# BackPlane.net
KiCad netlist of a schematic drawn in EAGLE
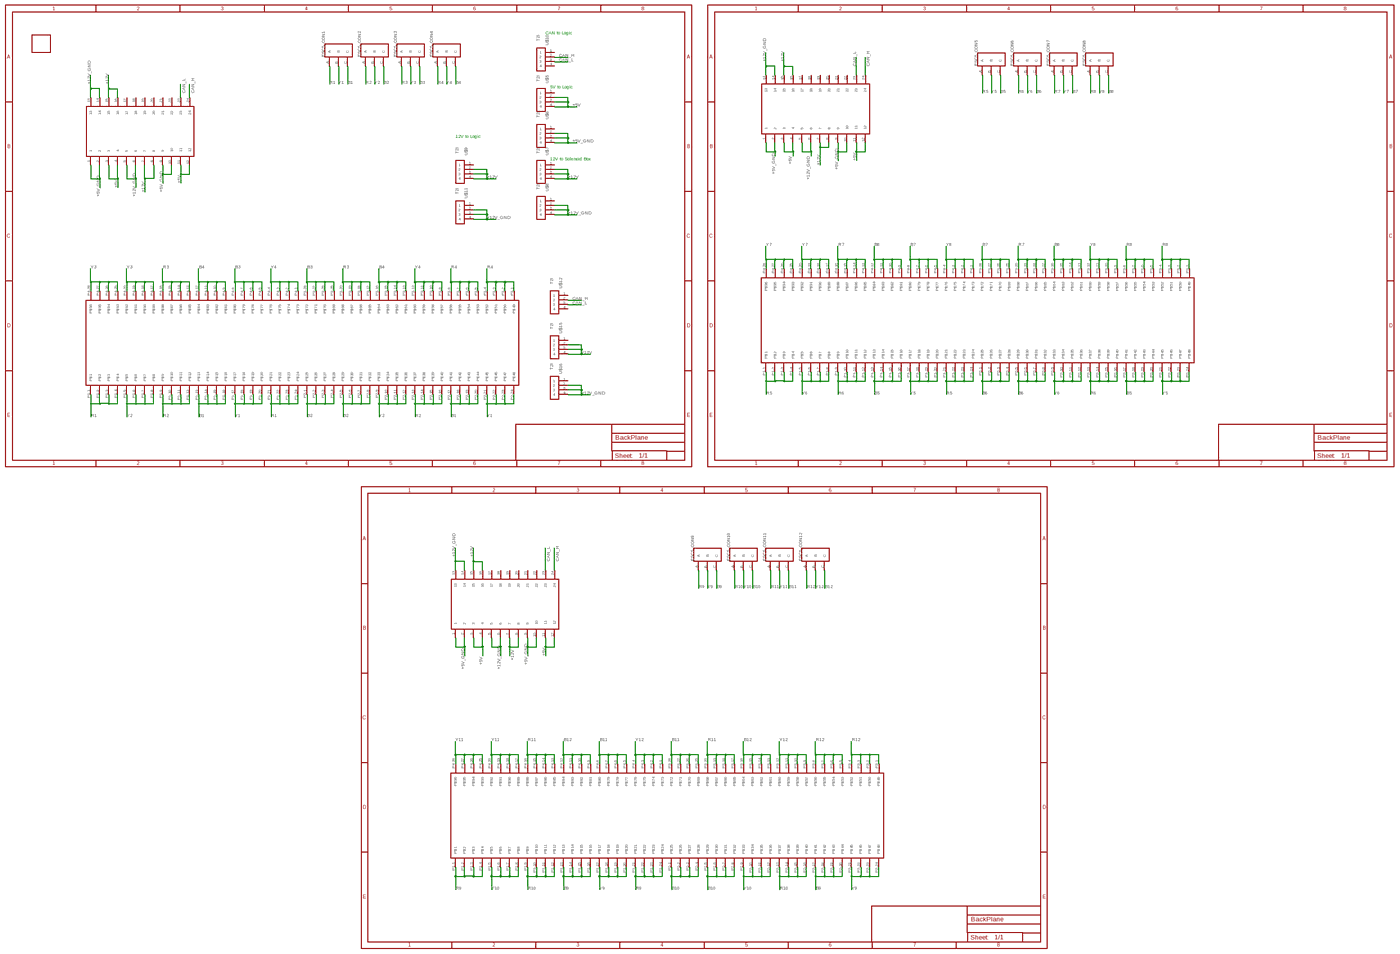
[diagram p0: schematic, sheet 1, overview]
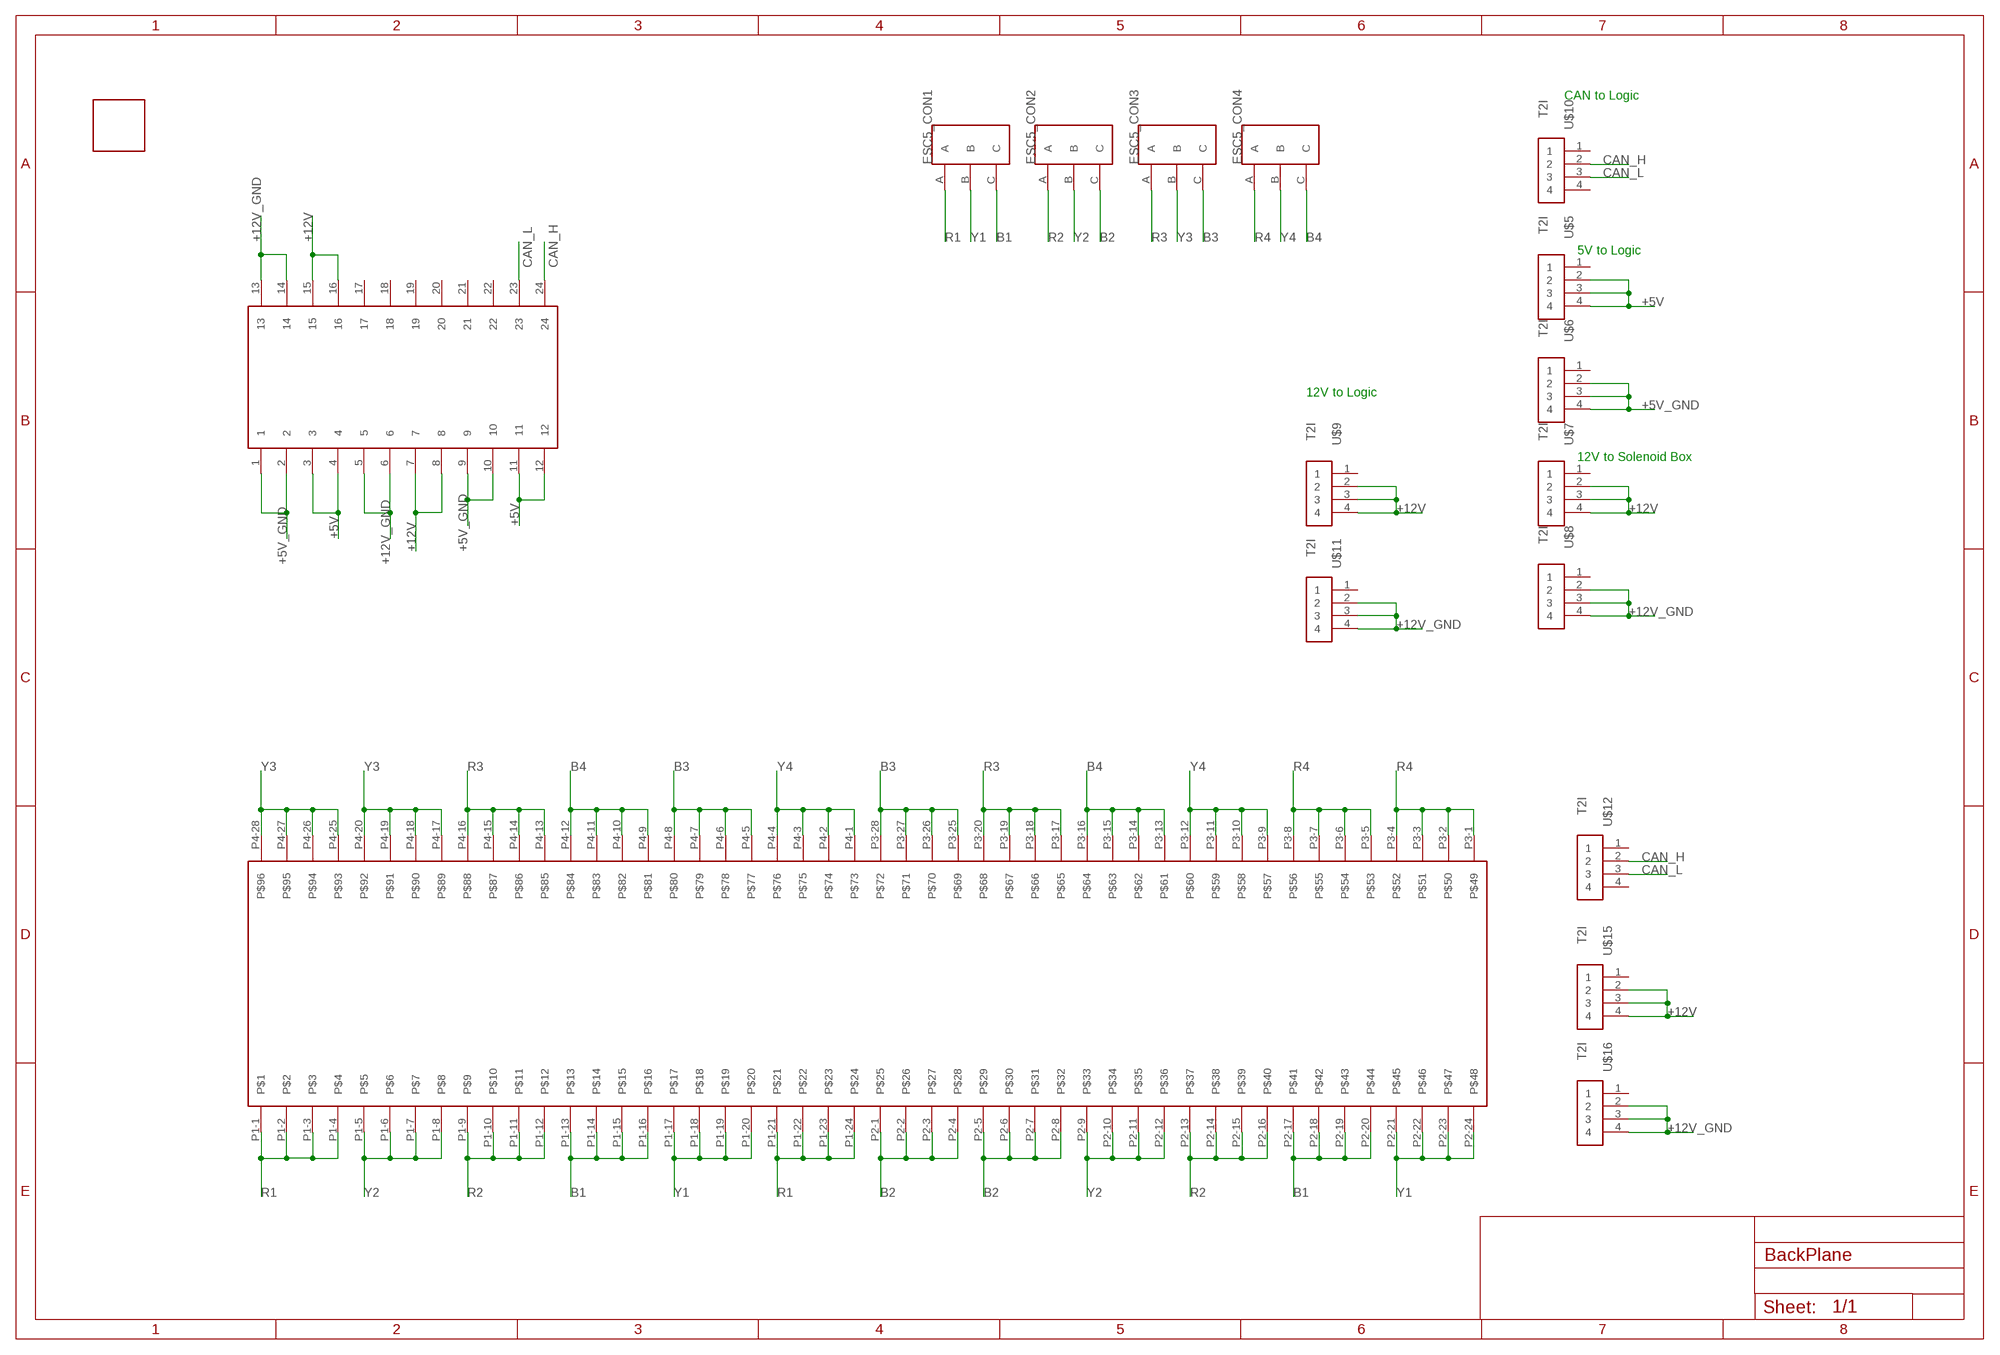
[diagram p1: schematic, sheet 1, part 1 of 4]
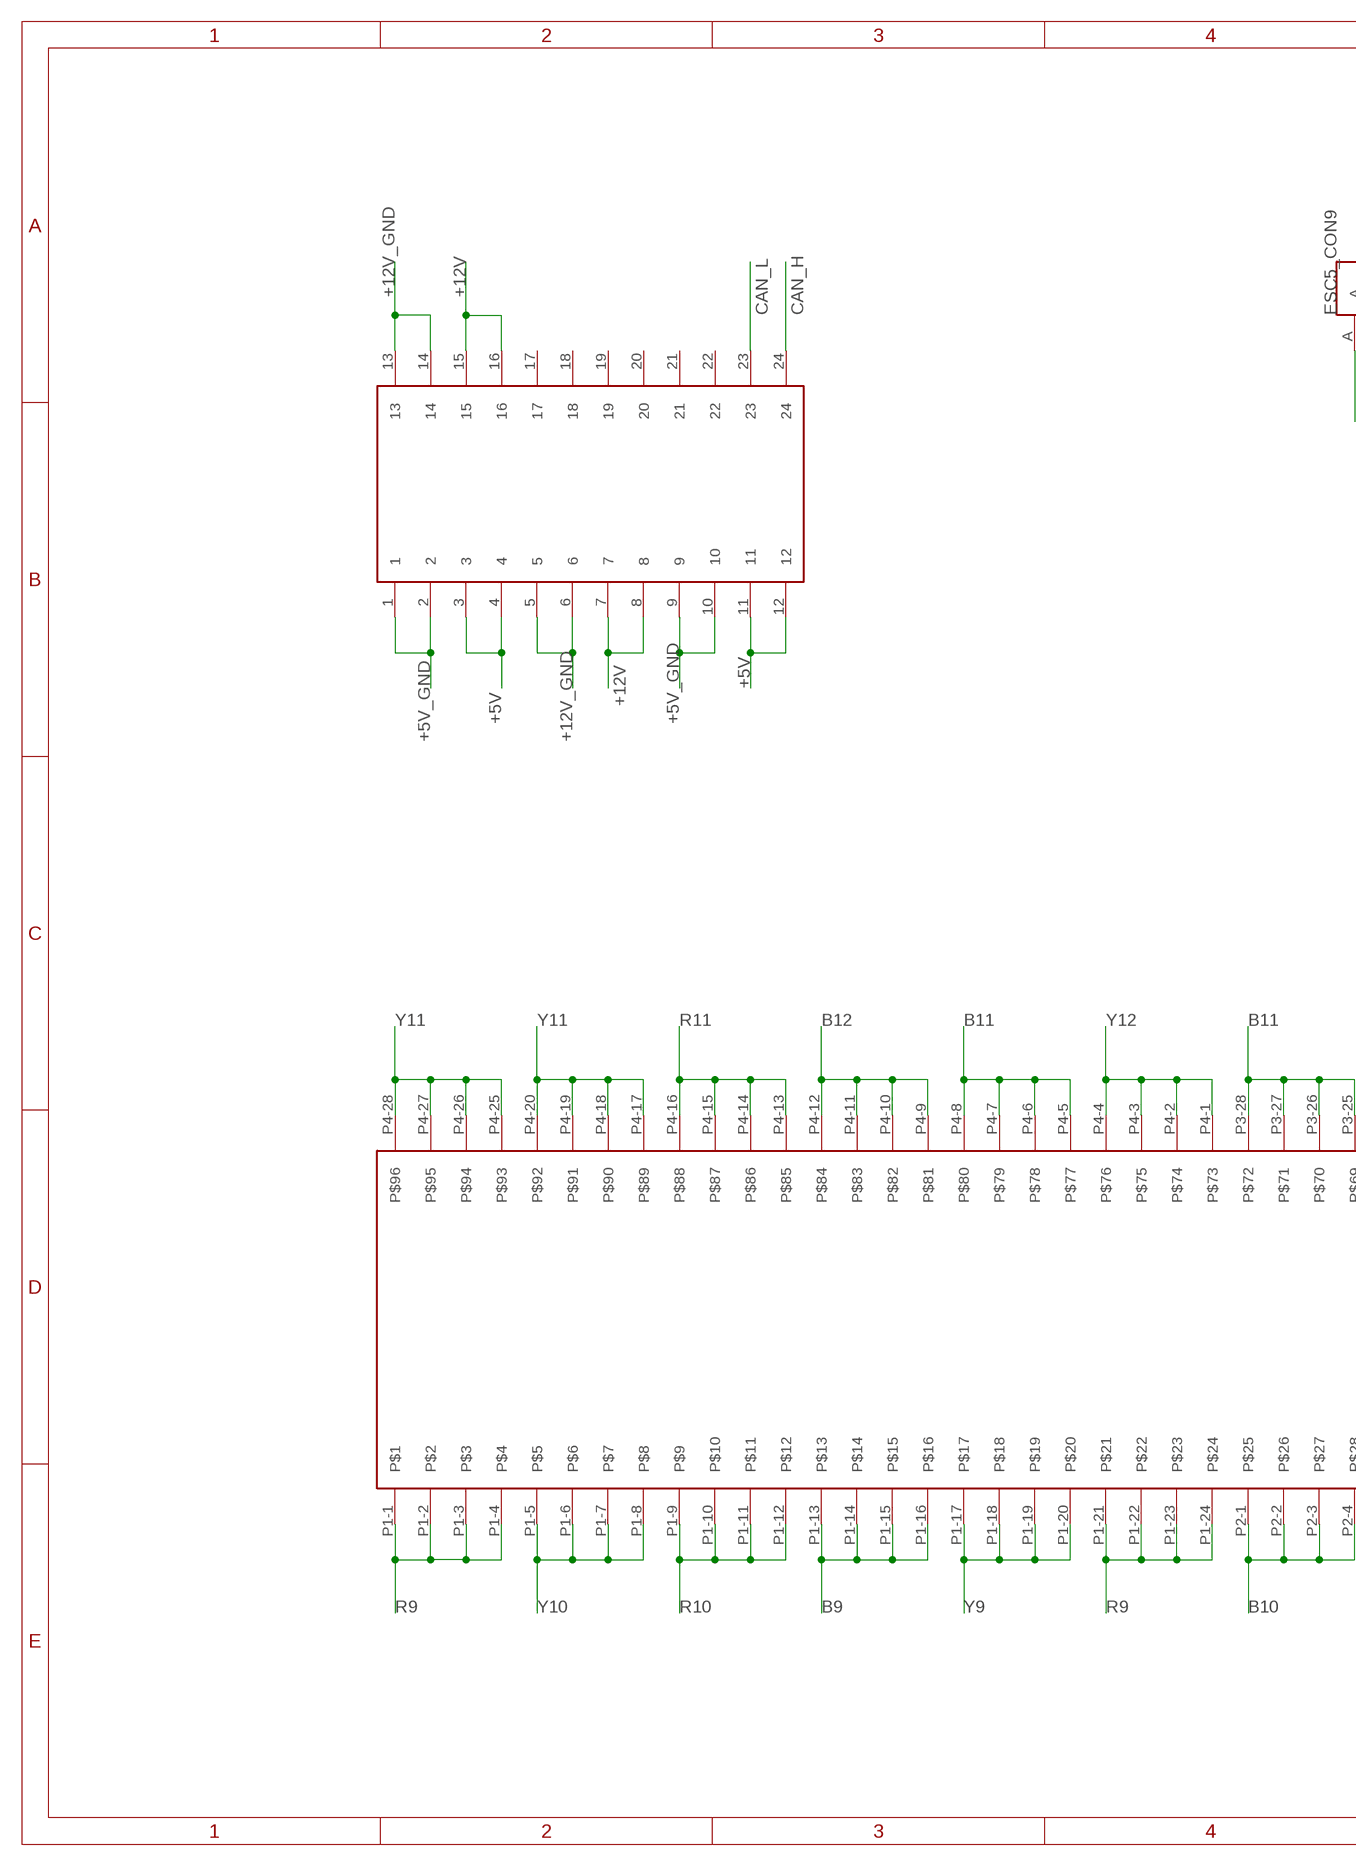
[diagram p2: schematic, sheet 1, part 2 of 4]
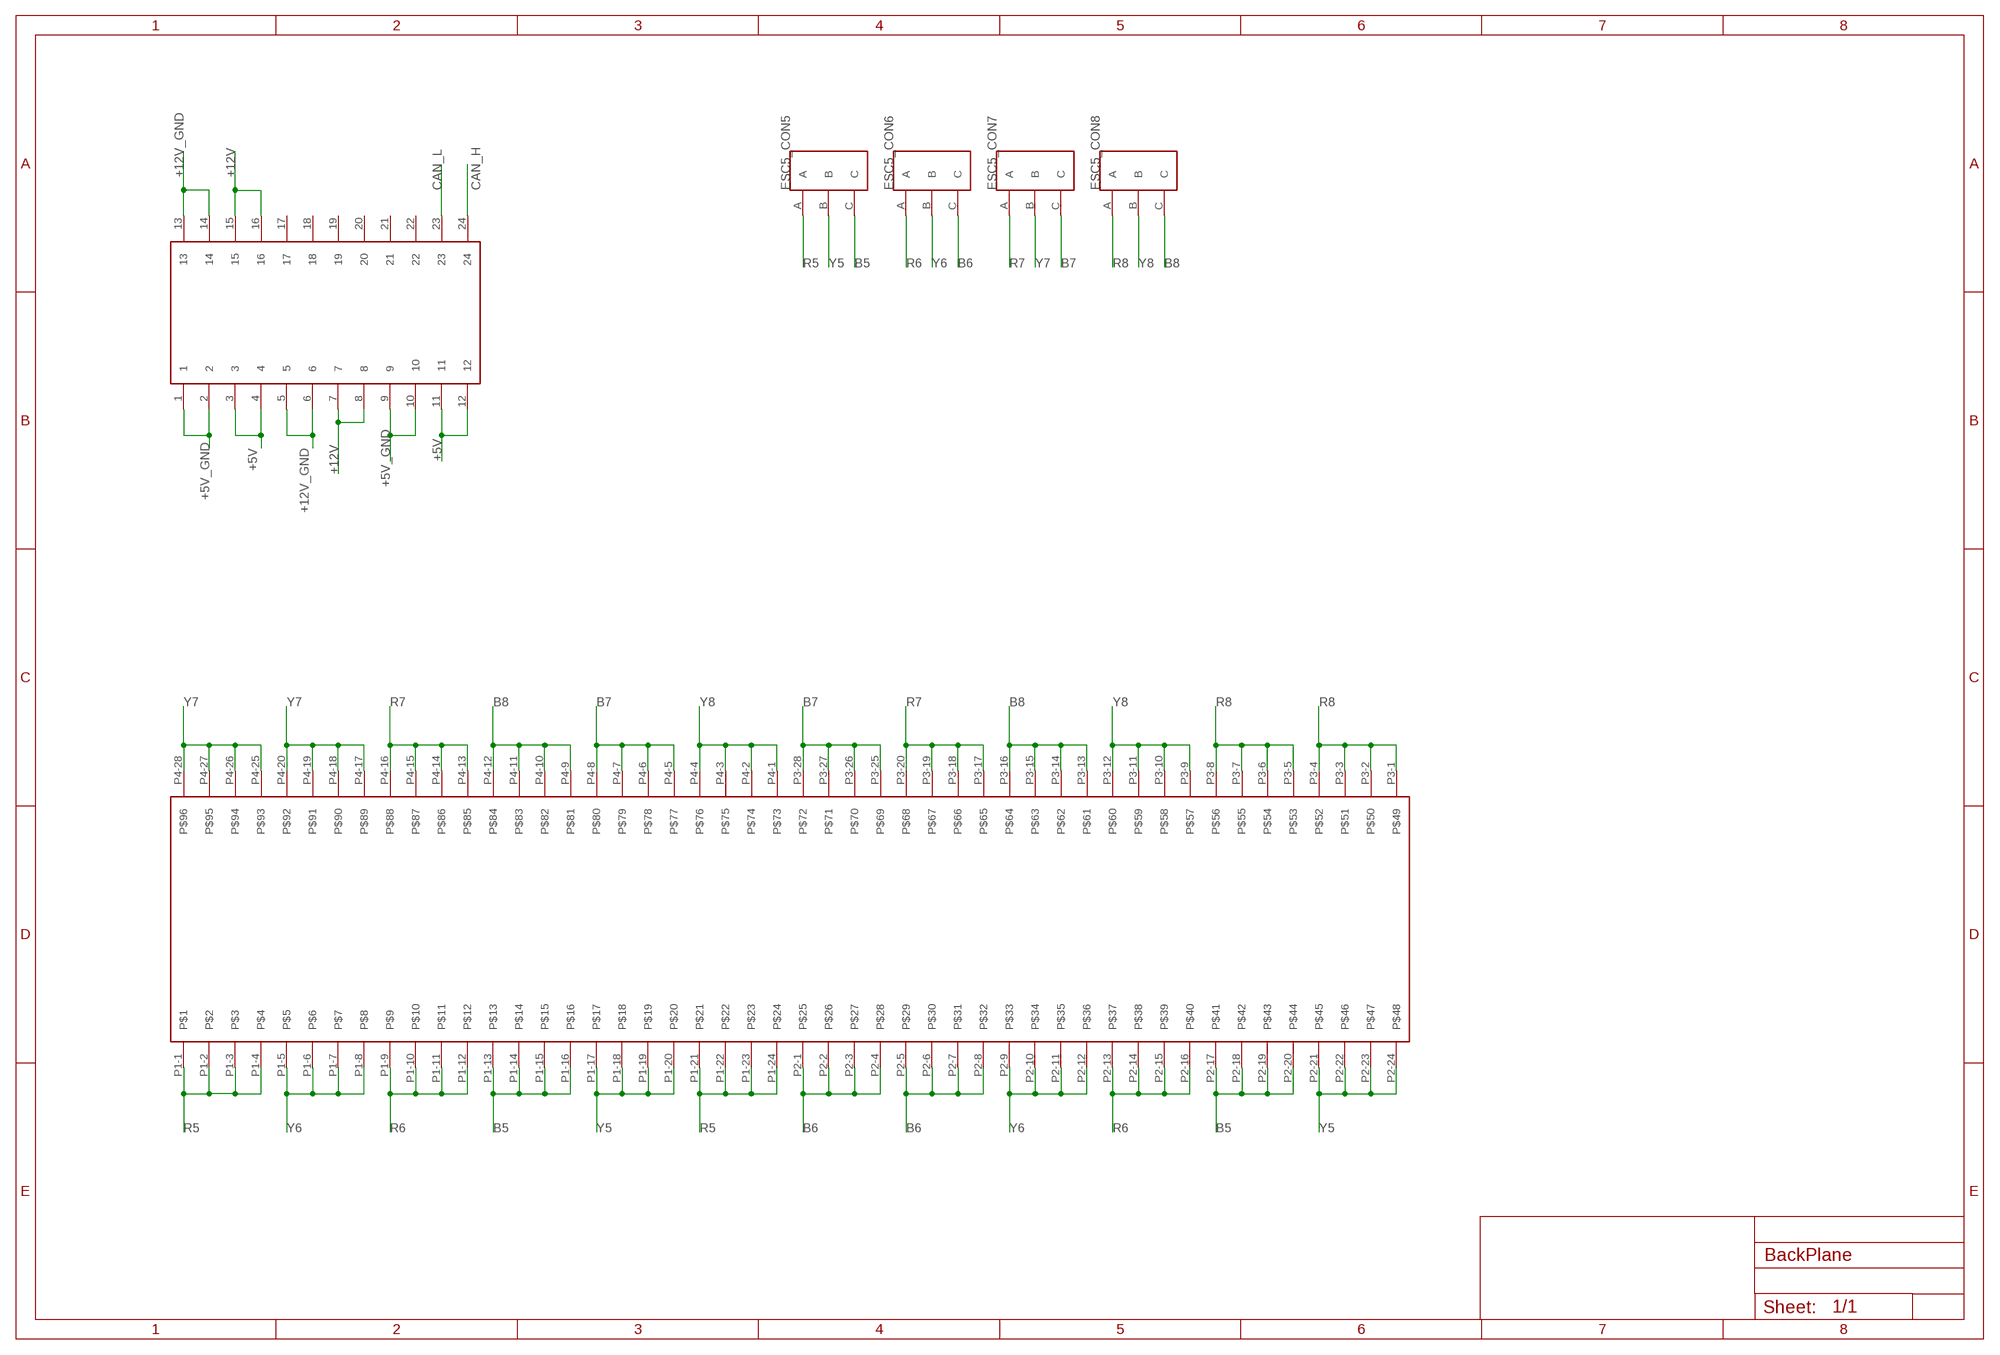
[diagram p3: schematic, sheet 1, part 3 of 4]
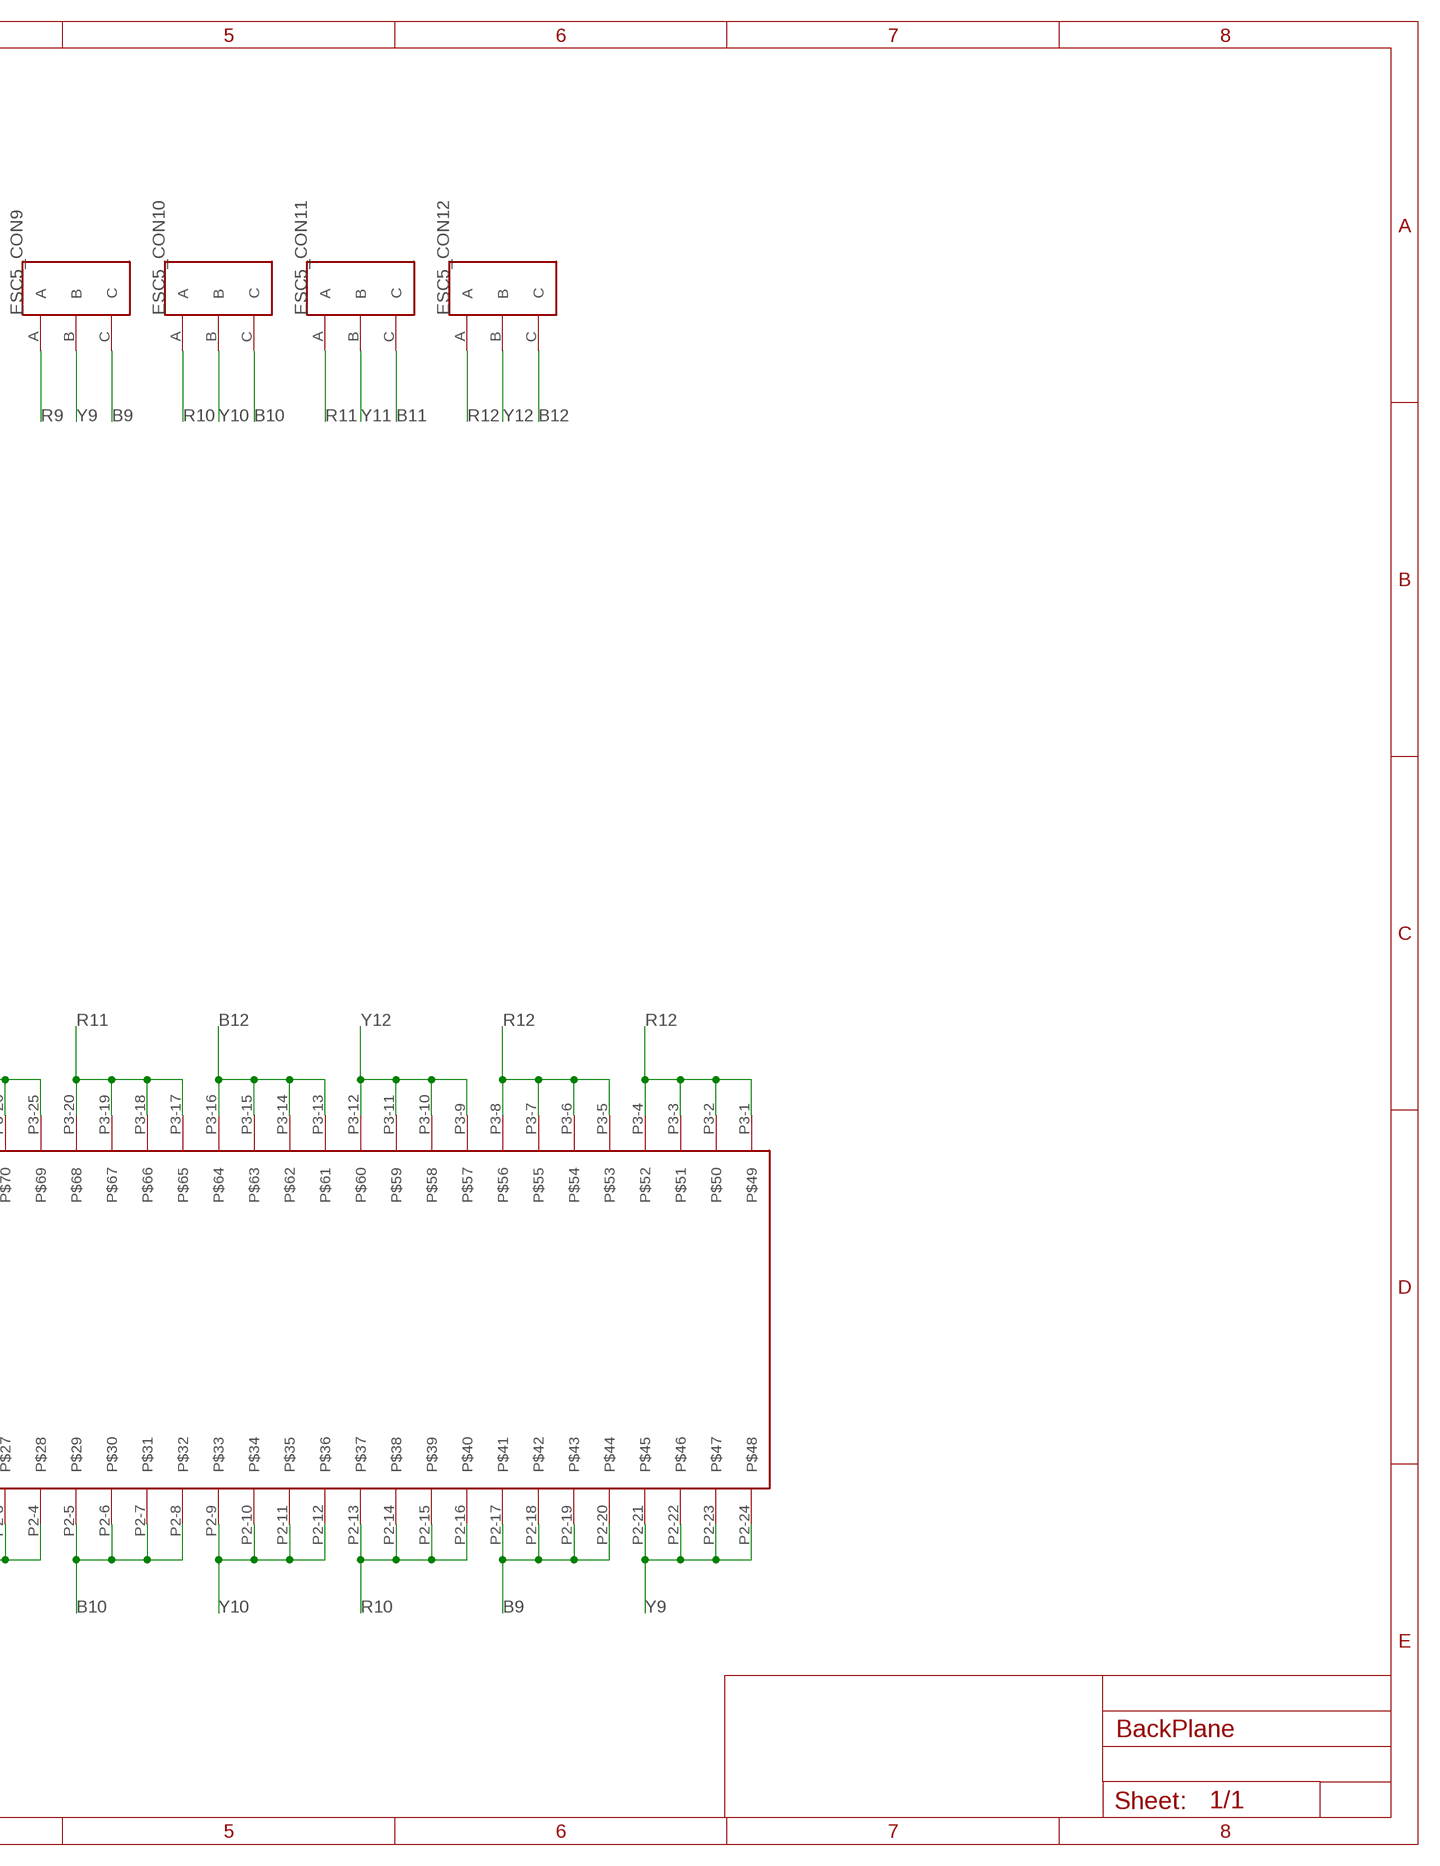
[diagram p4: schematic, sheet 1, part 4 of 4]

(export (version "E")
  (design (tool "Eeschema 10.0.6"))
  (components
    (comp (ref "ESC5_CON1")
      (value "3PINCONNECTOR")
      (footprint "eagle-import:3PINCONNECTOR")
      (libsource (lib "eagle-import") (part "3PINCONNECTOR"))
    )
    (comp (ref "ESC5_CON2")
      (value "3PINCONNECTOR")
      (footprint "eagle-import:3PINCONNECTOR")
      (libsource (lib "eagle-import") (part "3PINCONNECTOR"))
    )
    (comp (ref "ESC5_CON3")
      (value "3PINCONNECTOR")
      (footprint "eagle-import:3PINCONNECTOR")
      (libsource (lib "eagle-import") (part "3PINCONNECTOR"))
    )
    (comp (ref "ESC5_CON4")
      (value "3PINCONNECTOR")
      (footprint "eagle-import:3PINCONNECTOR")
      (libsource (lib "eagle-import") (part "3PINCONNECTOR"))
    )
    (comp (ref "ESC5_CON5")
      (value "3PINCONNECTOR")
      (footprint "eagle-import:3PINCONNECTOR")
      (libsource (lib "eagle-import") (part "3PINCONNECTOR"))
    )
    (comp (ref "ESC5_CON6")
      (value "3PINCONNECTOR")
      (footprint "eagle-import:3PINCONNECTOR")
      (libsource (lib "eagle-import") (part "3PINCONNECTOR"))
    )
    (comp (ref "ESC5_CON7")
      (value "3PINCONNECTOR")
      (footprint "eagle-import:3PINCONNECTOR")
      (libsource (lib "eagle-import") (part "3PINCONNECTOR"))
    )
    (comp (ref "ESC5_CON8")
      (value "3PINCONNECTOR")
      (footprint "eagle-import:3PINCONNECTOR")
      (libsource (lib "eagle-import") (part "3PINCONNECTOR"))
    )
    (comp (ref "ESC5_CON9")
      (value "3PINCONNECTOR")
      (footprint "eagle-import:3PINCONNECTOR")
      (libsource (lib "eagle-import") (part "3PINCONNECTOR"))
    )
    (comp (ref "ESC5_CON10")
      (value "3PINCONNECTOR")
      (footprint "eagle-import:3PINCONNECTOR")
      (libsource (lib "eagle-import") (part "3PINCONNECTOR"))
    )
    (comp (ref "ESC5_CON11")
      (value "3PINCONNECTOR")
      (footprint "eagle-import:3PINCONNECTOR")
      (libsource (lib "eagle-import") (part "3PINCONNECTOR"))
    )
    (comp (ref "ESC5_CON12")
      (value "3PINCONNECTOR")
      (footprint "eagle-import:3PINCONNECTOR")
      (libsource (lib "eagle-import") (part "3PINCONNECTOR"))
    )
    (comp (ref "U$1")
      (value "BOARDBKP")
      (footprint "eagle-import:BKP")
      (libsource (lib "eagle-import") (part "BOARDBKP"))
    )
    (comp (ref "U$2")
      (value "THICC_CONNECTOR")
      (footprint "eagle-import:THICC_CONNECTOR")
      (libsource (lib "eagle-import") (part "THICC_CONNECTOR"))
    )
    (comp (ref "U$3")
      (value "THICC_CONNECTOR")
      (footprint "eagle-import:THICC_CONNECTOR")
      (libsource (lib "eagle-import") (part "THICC_CONNECTOR"))
    )
    (comp (ref "U$4")
      (value "THICC_CONNECTOR")
      (footprint "eagle-import:THICC_CONNECTOR")
      (libsource (lib "eagle-import") (part "THICC_CONNECTOR"))
    )
    (comp (ref "U$5")
      (value "T2I")
      (footprint "eagle-import:T2I")
      (libsource (lib "eagle-import") (part "T2I"))
    )
    (comp (ref "U$6")
      (value "T2I")
      (footprint "eagle-import:T2I")
      (libsource (lib "eagle-import") (part "T2I"))
    )
    (comp (ref "U$7")
      (value "T2I")
      (footprint "eagle-import:T2I")
      (libsource (lib "eagle-import") (part "T2I"))
    )
    (comp (ref "U$8")
      (value "T2I")
      (footprint "eagle-import:T2I")
      (libsource (lib "eagle-import") (part "T2I"))
    )
    (comp (ref "U$9")
      (value "T2I")
      (footprint "eagle-import:T2I")
      (libsource (lib "eagle-import") (part "T2I"))
    )
    (comp (ref "U$10")
      (value "T2I")
      (footprint "eagle-import:T2I")
      (libsource (lib "eagle-import") (part "T2I"))
    )
    (comp (ref "U$11")
      (value "T2I")
      (footprint "eagle-import:T2I")
      (libsource (lib "eagle-import") (part "T2I"))
    )
    (comp (ref "U$12")
      (value "T2I")
      (footprint "eagle-import:T2I")
      (libsource (lib "eagle-import") (part "T2I"))
    )
    (comp (ref "U$15")
      (value "T2I")
      (footprint "eagle-import:T2I")
      (libsource (lib "eagle-import") (part "T2I"))
    )
    (comp (ref "U$16")
      (value "T2I")
      (footprint "eagle-import:T2I")
      (libsource (lib "eagle-import") (part "T2I"))
    )
  )
  (nets
    (net (code "1") (name "/+5V") (class "Default")
      (node (ref "U$2") (pin "11") (pinfunction "11_11") (pintype "bidirectional"))
      (node (ref "U$2") (pin "12") (pinfunction "12_12") (pintype "bidirectional"))
      (node (ref "U$2") (pin "3") (pinfunction "3_3") (pintype "bidirectional"))
      (node (ref "U$2") (pin "4") (pinfunction "4_4") (pintype "bidirectional"))
      (node (ref "U$3") (pin "11") (pinfunction "11_11") (pintype "bidirectional"))
      (node (ref "U$3") (pin "12") (pinfunction "12_12") (pintype "bidirectional"))
      (node (ref "U$3") (pin "3") (pinfunction "3_3") (pintype "bidirectional"))
      (node (ref "U$3") (pin "4") (pinfunction "4_4") (pintype "bidirectional"))
      (node (ref "U$4") (pin "11") (pinfunction "11_11") (pintype "bidirectional"))
      (node (ref "U$4") (pin "12") (pinfunction "12_12") (pintype "bidirectional"))
      (node (ref "U$4") (pin "3") (pinfunction "3_3") (pintype "bidirectional"))
      (node (ref "U$4") (pin "4") (pinfunction "4_4") (pintype "bidirectional"))
      (node (ref "U$5") (pin "2") (pinfunction "2_2") (pintype "bidirectional"))
      (node (ref "U$5") (pin "3") (pinfunction "3_3") (pintype "bidirectional"))
      (node (ref "U$5") (pin "4") (pinfunction "4_4") (pintype "bidirectional"))
    )
    (net (code "2") (name "/+5V_GND") (class "Default")
      (node (ref "U$2") (pin "1") (pinfunction "1_1") (pintype "bidirectional"))
      (node (ref "U$2") (pin "10") (pinfunction "10_10") (pintype "bidirectional"))
      (node (ref "U$2") (pin "2") (pinfunction "2_2") (pintype "bidirectional"))
      (node (ref "U$2") (pin "9") (pinfunction "9_9") (pintype "bidirectional"))
      (node (ref "U$3") (pin "1") (pinfunction "1_1") (pintype "bidirectional"))
      (node (ref "U$3") (pin "10") (pinfunction "10_10") (pintype "bidirectional"))
      (node (ref "U$3") (pin "2") (pinfunction "2_2") (pintype "bidirectional"))
      (node (ref "U$3") (pin "9") (pinfunction "9_9") (pintype "bidirectional"))
      (node (ref "U$4") (pin "1") (pinfunction "1_1") (pintype "bidirectional"))
      (node (ref "U$4") (pin "10") (pinfunction "10_10") (pintype "bidirectional"))
      (node (ref "U$4") (pin "2") (pinfunction "2_2") (pintype "bidirectional"))
      (node (ref "U$4") (pin "9") (pinfunction "9_9") (pintype "bidirectional"))
      (node (ref "U$6") (pin "2") (pinfunction "2_2") (pintype "bidirectional"))
      (node (ref "U$6") (pin "3") (pinfunction "3_3") (pintype "bidirectional"))
      (node (ref "U$6") (pin "4") (pinfunction "4_4") (pintype "bidirectional"))
    )
    (net (code "3") (name "/+12V") (class "Default")
      (node (ref "U$15") (pin "2") (pinfunction "2_2") (pintype "bidirectional"))
      (node (ref "U$15") (pin "3") (pinfunction "3_3") (pintype "bidirectional"))
      (node (ref "U$15") (pin "4") (pinfunction "4_4") (pintype "bidirectional"))
      (node (ref "U$2") (pin "15") (pinfunction "15_15") (pintype "bidirectional"))
      (node (ref "U$2") (pin "16") (pinfunction "16_16") (pintype "bidirectional"))
      (node (ref "U$2") (pin "7") (pinfunction "7_7") (pintype "bidirectional"))
      (node (ref "U$2") (pin "8") (pinfunction "8_8") (pintype "bidirectional"))
      (node (ref "U$3") (pin "15") (pinfunction "15_15") (pintype "bidirectional"))
      (node (ref "U$3") (pin "16") (pinfunction "16_16") (pintype "bidirectional"))
      (node (ref "U$3") (pin "7") (pinfunction "7_7") (pintype "bidirectional"))
      (node (ref "U$3") (pin "8") (pinfunction "8_8") (pintype "bidirectional"))
      (node (ref "U$4") (pin "15") (pinfunction "15_15") (pintype "bidirectional"))
      (node (ref "U$4") (pin "16") (pinfunction "16_16") (pintype "bidirectional"))
      (node (ref "U$4") (pin "7") (pinfunction "7_7") (pintype "bidirectional"))
      (node (ref "U$4") (pin "8") (pinfunction "8_8") (pintype "bidirectional"))
      (node (ref "U$7") (pin "2") (pinfunction "2_2") (pintype "bidirectional"))
      (node (ref "U$7") (pin "3") (pinfunction "3_3") (pintype "bidirectional"))
      (node (ref "U$7") (pin "4") (pinfunction "4_4") (pintype "bidirectional"))
      (node (ref "U$9") (pin "2") (pinfunction "2_2") (pintype "bidirectional"))
      (node (ref "U$9") (pin "3") (pinfunction "3_3") (pintype "bidirectional"))
      (node (ref "U$9") (pin "4") (pinfunction "4_4") (pintype "bidirectional"))
    )
    (net (code "4") (name "/+12V_GND") (class "Default")
      (node (ref "U$11") (pin "2") (pinfunction "2_2") (pintype "bidirectional"))
      (node (ref "U$11") (pin "3") (pinfunction "3_3") (pintype "bidirectional"))
      (node (ref "U$11") (pin "4") (pinfunction "4_4") (pintype "bidirectional"))
      (node (ref "U$16") (pin "2") (pinfunction "2_2") (pintype "bidirectional"))
      (node (ref "U$16") (pin "3") (pinfunction "3_3") (pintype "bidirectional"))
      (node (ref "U$16") (pin "4") (pinfunction "4_4") (pintype "bidirectional"))
      (node (ref "U$2") (pin "13") (pinfunction "13_13") (pintype "bidirectional"))
      (node (ref "U$2") (pin "14") (pinfunction "14_14") (pintype "bidirectional"))
      (node (ref "U$2") (pin "5") (pinfunction "5_5") (pintype "bidirectional"))
      (node (ref "U$2") (pin "6") (pinfunction "6_6") (pintype "bidirectional"))
      (node (ref "U$3") (pin "13") (pinfunction "13_13") (pintype "bidirectional"))
      (node (ref "U$3") (pin "14") (pinfunction "14_14") (pintype "bidirectional"))
      (node (ref "U$3") (pin "5") (pinfunction "5_5") (pintype "bidirectional"))
      (node (ref "U$3") (pin "6") (pinfunction "6_6") (pintype "bidirectional"))
      (node (ref "U$4") (pin "13") (pinfunction "13_13") (pintype "bidirectional"))
      (node (ref "U$4") (pin "14") (pinfunction "14_14") (pintype "bidirectional"))
      (node (ref "U$4") (pin "5") (pinfunction "5_5") (pintype "bidirectional"))
      (node (ref "U$4") (pin "6") (pinfunction "6_6") (pintype "bidirectional"))
      (node (ref "U$8") (pin "2") (pinfunction "2_2") (pintype "bidirectional"))
      (node (ref "U$8") (pin "3") (pinfunction "3_3") (pintype "bidirectional"))
      (node (ref "U$8") (pin "4") (pinfunction "4_4") (pintype "bidirectional"))
    )
    (net (code "5") (name "/B1") (class "Default")
      (node (ref "ESC5_CON1") (pin "C") (pinfunction "C_C") (pintype "bidirectional"))
      (node (ref "U$2") (pin "P1-13") (pinfunction "P$13_P1-13") (pintype "bidirectional"))
      (node (ref "U$2") (pin "P1-14") (pinfunction "P$14_P1-14") (pintype "bidirectional"))
      (node (ref "U$2") (pin "P1-15") (pinfunction "P$15_P1-15") (pintype "bidirectional"))
      (node (ref "U$2") (pin "P1-16") (pinfunction "P$16_P1-16") (pintype "bidirectional"))
      (node (ref "U$2") (pin "P2-17") (pinfunction "P$41_P2-17") (pintype "bidirectional"))
      (node (ref "U$2") (pin "P2-18") (pinfunction "P$42_P2-18") (pintype "bidirectional"))
      (node (ref "U$2") (pin "P2-19") (pinfunction "P$43_P2-19") (pintype "bidirectional"))
      (node (ref "U$2") (pin "P2-20") (pinfunction "P$44_P2-20") (pintype "bidirectional"))
    )
    (net (code "6") (name "/B2") (class "Default")
      (node (ref "ESC5_CON2") (pin "C") (pinfunction "C_C") (pintype "bidirectional"))
      (node (ref "U$2") (pin "P2-1") (pinfunction "P$25_P2-1") (pintype "bidirectional"))
      (node (ref "U$2") (pin "P2-2") (pinfunction "P$26_P2-2") (pintype "bidirectional"))
      (node (ref "U$2") (pin "P2-3") (pinfunction "P$27_P2-3") (pintype "bidirectional"))
      (node (ref "U$2") (pin "P2-4") (pinfunction "P$28_P2-4") (pintype "bidirectional"))
      (node (ref "U$2") (pin "P2-5") (pinfunction "P$29_P2-5") (pintype "bidirectional"))
      (node (ref "U$2") (pin "P2-6") (pinfunction "P$30_P2-6") (pintype "bidirectional"))
      (node (ref "U$2") (pin "P2-7") (pinfunction "P$31_P2-7") (pintype "bidirectional"))
      (node (ref "U$2") (pin "P2-8") (pinfunction "P$32_P2-8") (pintype "bidirectional"))
    )
    (net (code "7") (name "/B3") (class "Default")
      (node (ref "ESC5_CON3") (pin "C") (pinfunction "C_C") (pintype "bidirectional"))
      (node (ref "U$2") (pin "P3-25") (pinfunction "P$69_P3-25") (pintype "bidirectional"))
      (node (ref "U$2") (pin "P3-26") (pinfunction "P$70_P3-26") (pintype "bidirectional"))
      (node (ref "U$2") (pin "P3-27") (pinfunction "P$71_P3-27") (pintype "bidirectional"))
      (node (ref "U$2") (pin "P3-28") (pinfunction "P$72_P3-28") (pintype "bidirectional"))
      (node (ref "U$2") (pin "P4-5") (pinfunction "P$77_P4-5") (pintype "bidirectional"))
      (node (ref "U$2") (pin "P4-6") (pinfunction "P$78_P4-6") (pintype "bidirectional"))
      (node (ref "U$2") (pin "P4-7") (pinfunction "P$79_P4-7") (pintype "bidirectional"))
      (node (ref "U$2") (pin "P4-8") (pinfunction "P$80_P4-8") (pintype "bidirectional"))
    )
    (net (code "8") (name "/B4") (class "Default")
      (node (ref "ESC5_CON4") (pin "C") (pinfunction "C_C") (pintype "bidirectional"))
      (node (ref "U$2") (pin "P3-13") (pinfunction "P$61_P3-13") (pintype "bidirectional"))
      (node (ref "U$2") (pin "P3-14") (pinfunction "P$62_P3-14") (pintype "bidirectional"))
      (node (ref "U$2") (pin "P3-15") (pinfunction "P$63_P3-15") (pintype "bidirectional"))
      (node (ref "U$2") (pin "P3-16") (pinfunction "P$64_P3-16") (pintype "bidirectional"))
      (node (ref "U$2") (pin "P4-10") (pinfunction "P$82_P4-10") (pintype "bidirectional"))
      (node (ref "U$2") (pin "P4-11") (pinfunction "P$83_P4-11") (pintype "bidirectional"))
      (node (ref "U$2") (pin "P4-12") (pinfunction "P$84_P4-12") (pintype "bidirectional"))
      (node (ref "U$2") (pin "P4-9") (pinfunction "P$81_P4-9") (pintype "bidirectional"))
    )
    (net (code "9") (name "/B5") (class "Default")
      (node (ref "ESC5_CON5") (pin "C") (pinfunction "C_C") (pintype "bidirectional"))
      (node (ref "U$3") (pin "P1-13") (pinfunction "P$13_P1-13") (pintype "bidirectional"))
      (node (ref "U$3") (pin "P1-14") (pinfunction "P$14_P1-14") (pintype "bidirectional"))
      (node (ref "U$3") (pin "P1-15") (pinfunction "P$15_P1-15") (pintype "bidirectional"))
      (node (ref "U$3") (pin "P1-16") (pinfunction "P$16_P1-16") (pintype "bidirectional"))
      (node (ref "U$3") (pin "P2-17") (pinfunction "P$41_P2-17") (pintype "bidirectional"))
      (node (ref "U$3") (pin "P2-18") (pinfunction "P$42_P2-18") (pintype "bidirectional"))
      (node (ref "U$3") (pin "P2-19") (pinfunction "P$43_P2-19") (pintype "bidirectional"))
      (node (ref "U$3") (pin "P2-20") (pinfunction "P$44_P2-20") (pintype "bidirectional"))
    )
    (net (code "10") (name "/B6") (class "Default")
      (node (ref "ESC5_CON6") (pin "C") (pinfunction "C_C") (pintype "bidirectional"))
      (node (ref "U$3") (pin "P2-1") (pinfunction "P$25_P2-1") (pintype "bidirectional"))
      (node (ref "U$3") (pin "P2-2") (pinfunction "P$26_P2-2") (pintype "bidirectional"))
      (node (ref "U$3") (pin "P2-3") (pinfunction "P$27_P2-3") (pintype "bidirectional"))
      (node (ref "U$3") (pin "P2-4") (pinfunction "P$28_P2-4") (pintype "bidirectional"))
      (node (ref "U$3") (pin "P2-5") (pinfunction "P$29_P2-5") (pintype "bidirectional"))
      (node (ref "U$3") (pin "P2-6") (pinfunction "P$30_P2-6") (pintype "bidirectional"))
      (node (ref "U$3") (pin "P2-7") (pinfunction "P$31_P2-7") (pintype "bidirectional"))
      (node (ref "U$3") (pin "P2-8") (pinfunction "P$32_P2-8") (pintype "bidirectional"))
    )
    (net (code "11") (name "/B7") (class "Default")
      (node (ref "ESC5_CON7") (pin "C") (pinfunction "C_C") (pintype "bidirectional"))
      (node (ref "U$3") (pin "P3-25") (pinfunction "P$69_P3-25") (pintype "bidirectional"))
      (node (ref "U$3") (pin "P3-26") (pinfunction "P$70_P3-26") (pintype "bidirectional"))
      (node (ref "U$3") (pin "P3-27") (pinfunction "P$71_P3-27") (pintype "bidirectional"))
      (node (ref "U$3") (pin "P3-28") (pinfunction "P$72_P3-28") (pintype "bidirectional"))
      (node (ref "U$3") (pin "P4-5") (pinfunction "P$77_P4-5") (pintype "bidirectional"))
      (node (ref "U$3") (pin "P4-6") (pinfunction "P$78_P4-6") (pintype "bidirectional"))
      (node (ref "U$3") (pin "P4-7") (pinfunction "P$79_P4-7") (pintype "bidirectional"))
      (node (ref "U$3") (pin "P4-8") (pinfunction "P$80_P4-8") (pintype "bidirectional"))
    )
    (net (code "12") (name "/B8") (class "Default")
      (node (ref "ESC5_CON8") (pin "C") (pinfunction "C_C") (pintype "bidirectional"))
      (node (ref "U$3") (pin "P3-13") (pinfunction "P$61_P3-13") (pintype "bidirectional"))
      (node (ref "U$3") (pin "P3-14") (pinfunction "P$62_P3-14") (pintype "bidirectional"))
      (node (ref "U$3") (pin "P3-15") (pinfunction "P$63_P3-15") (pintype "bidirectional"))
      (node (ref "U$3") (pin "P3-16") (pinfunction "P$64_P3-16") (pintype "bidirectional"))
      (node (ref "U$3") (pin "P4-10") (pinfunction "P$82_P4-10") (pintype "bidirectional"))
      (node (ref "U$3") (pin "P4-11") (pinfunction "P$83_P4-11") (pintype "bidirectional"))
      (node (ref "U$3") (pin "P4-12") (pinfunction "P$84_P4-12") (pintype "bidirectional"))
      (node (ref "U$3") (pin "P4-9") (pinfunction "P$81_P4-9") (pintype "bidirectional"))
    )
    (net (code "13") (name "/B9") (class "Default")
      (node (ref "ESC5_CON9") (pin "C") (pinfunction "C_C") (pintype "bidirectional"))
      (node (ref "U$4") (pin "P1-13") (pinfunction "P$13_P1-13") (pintype "bidirectional"))
      (node (ref "U$4") (pin "P1-14") (pinfunction "P$14_P1-14") (pintype "bidirectional"))
      (node (ref "U$4") (pin "P1-15") (pinfunction "P$15_P1-15") (pintype "bidirectional"))
      (node (ref "U$4") (pin "P1-16") (pinfunction "P$16_P1-16") (pintype "bidirectional"))
      (node (ref "U$4") (pin "P2-17") (pinfunction "P$41_P2-17") (pintype "bidirectional"))
      (node (ref "U$4") (pin "P2-18") (pinfunction "P$42_P2-18") (pintype "bidirectional"))
      (node (ref "U$4") (pin "P2-19") (pinfunction "P$43_P2-19") (pintype "bidirectional"))
      (node (ref "U$4") (pin "P2-20") (pinfunction "P$44_P2-20") (pintype "bidirectional"))
    )
    (net (code "14") (name "/B10") (class "Default")
      (node (ref "ESC5_CON10") (pin "C") (pinfunction "C_C") (pintype "bidirectional"))
      (node (ref "U$4") (pin "P2-1") (pinfunction "P$25_P2-1") (pintype "bidirectional"))
      (node (ref "U$4") (pin "P2-2") (pinfunction "P$26_P2-2") (pintype "bidirectional"))
      (node (ref "U$4") (pin "P2-3") (pinfunction "P$27_P2-3") (pintype "bidirectional"))
      (node (ref "U$4") (pin "P2-4") (pinfunction "P$28_P2-4") (pintype "bidirectional"))
      (node (ref "U$4") (pin "P2-5") (pinfunction "P$29_P2-5") (pintype "bidirectional"))
      (node (ref "U$4") (pin "P2-6") (pinfunction "P$30_P2-6") (pintype "bidirectional"))
      (node (ref "U$4") (pin "P2-7") (pinfunction "P$31_P2-7") (pintype "bidirectional"))
      (node (ref "U$4") (pin "P2-8") (pinfunction "P$32_P2-8") (pintype "bidirectional"))
    )
    (net (code "15") (name "/B11") (class "Default")
      (node (ref "ESC5_CON11") (pin "C") (pinfunction "C_C") (pintype "bidirectional"))
      (node (ref "U$4") (pin "P3-25") (pinfunction "P$69_P3-25") (pintype "bidirectional"))
      (node (ref "U$4") (pin "P3-26") (pinfunction "P$70_P3-26") (pintype "bidirectional"))
      (node (ref "U$4") (pin "P3-27") (pinfunction "P$71_P3-27") (pintype "bidirectional"))
      (node (ref "U$4") (pin "P3-28") (pinfunction "P$72_P3-28") (pintype "bidirectional"))
      (node (ref "U$4") (pin "P4-5") (pinfunction "P$77_P4-5") (pintype "bidirectional"))
      (node (ref "U$4") (pin "P4-6") (pinfunction "P$78_P4-6") (pintype "bidirectional"))
      (node (ref "U$4") (pin "P4-7") (pinfunction "P$79_P4-7") (pintype "bidirectional"))
      (node (ref "U$4") (pin "P4-8") (pinfunction "P$80_P4-8") (pintype "bidirectional"))
    )
    (net (code "16") (name "/B12") (class "Default")
      (node (ref "ESC5_CON12") (pin "C") (pinfunction "C_C") (pintype "bidirectional"))
      (node (ref "U$4") (pin "P3-13") (pinfunction "P$61_P3-13") (pintype "bidirectional"))
      (node (ref "U$4") (pin "P3-14") (pinfunction "P$62_P3-14") (pintype "bidirectional"))
      (node (ref "U$4") (pin "P3-15") (pinfunction "P$63_P3-15") (pintype "bidirectional"))
      (node (ref "U$4") (pin "P3-16") (pinfunction "P$64_P3-16") (pintype "bidirectional"))
      (node (ref "U$4") (pin "P4-10") (pinfunction "P$82_P4-10") (pintype "bidirectional"))
      (node (ref "U$4") (pin "P4-11") (pinfunction "P$83_P4-11") (pintype "bidirectional"))
      (node (ref "U$4") (pin "P4-12") (pinfunction "P$84_P4-12") (pintype "bidirectional"))
      (node (ref "U$4") (pin "P4-9") (pinfunction "P$81_P4-9") (pintype "bidirectional"))
    )
    (net (code "17") (name "/CAN_H") (class "Default")
      (node (ref "U$10") (pin "2") (pinfunction "2_2") (pintype "bidirectional"))
      (node (ref "U$12") (pin "2") (pinfunction "2_2") (pintype "bidirectional"))
      (node (ref "U$2") (pin "24") (pinfunction "24_24") (pintype "bidirectional"))
      (node (ref "U$3") (pin "24") (pinfunction "24_24") (pintype "bidirectional"))
      (node (ref "U$4") (pin "24") (pinfunction "24_24") (pintype "bidirectional"))
    )
    (net (code "18") (name "/CAN_L") (class "Default")
      (node (ref "U$10") (pin "3") (pinfunction "3_3") (pintype "bidirectional"))
      (node (ref "U$12") (pin "3") (pinfunction "3_3") (pintype "bidirectional"))
      (node (ref "U$2") (pin "23") (pinfunction "23_23") (pintype "bidirectional"))
      (node (ref "U$3") (pin "23") (pinfunction "23_23") (pintype "bidirectional"))
      (node (ref "U$4") (pin "23") (pinfunction "23_23") (pintype "bidirectional"))
    )
    (net (code "19") (name "/R1") (class "Default")
      (node (ref "ESC5_CON1") (pin "A") (pinfunction "A_A") (pintype "bidirectional"))
      (node (ref "U$2") (pin "P1-1") (pinfunction "P$1_P1-1") (pintype "bidirectional"))
      (node (ref "U$2") (pin "P1-2") (pinfunction "P$2_P1-2") (pintype "bidirectional"))
      (node (ref "U$2") (pin "P1-21") (pinfunction "P$21_P1-21") (pintype "bidirectional"))
      (node (ref "U$2") (pin "P1-22") (pinfunction "P$22_P1-22") (pintype "bidirectional"))
      (node (ref "U$2") (pin "P1-23") (pinfunction "P$23_P1-23") (pintype "bidirectional"))
      (node (ref "U$2") (pin "P1-24") (pinfunction "P$24_P1-24") (pintype "bidirectional"))
      (node (ref "U$2") (pin "P1-3") (pinfunction "P$3_P1-3") (pintype "bidirectional"))
      (node (ref "U$2") (pin "P1-4") (pinfunction "P$4_P1-4") (pintype "bidirectional"))
    )
    (net (code "20") (name "/R2") (class "Default")
      (node (ref "ESC5_CON2") (pin "A") (pinfunction "A_A") (pintype "bidirectional"))
      (node (ref "U$2") (pin "P1-10") (pinfunction "P$10_P1-10") (pintype "bidirectional"))
      (node (ref "U$2") (pin "P1-11") (pinfunction "P$11_P1-11") (pintype "bidirectional"))
      (node (ref "U$2") (pin "P1-12") (pinfunction "P$12_P1-12") (pintype "bidirectional"))
      (node (ref "U$2") (pin "P1-9") (pinfunction "P$9_P1-9") (pintype "bidirectional"))
      (node (ref "U$2") (pin "P2-13") (pinfunction "P$37_P2-13") (pintype "bidirectional"))
      (node (ref "U$2") (pin "P2-14") (pinfunction "P$38_P2-14") (pintype "bidirectional"))
      (node (ref "U$2") (pin "P2-15") (pinfunction "P$39_P2-15") (pintype "bidirectional"))
      (node (ref "U$2") (pin "P2-16") (pinfunction "P$40_P2-16") (pintype "bidirectional"))
    )
    (net (code "21") (name "/R3") (class "Default")
      (node (ref "ESC5_CON3") (pin "A") (pinfunction "A_A") (pintype "bidirectional"))
      (node (ref "U$2") (pin "P3-17") (pinfunction "P$65_P3-17") (pintype "bidirectional"))
      (node (ref "U$2") (pin "P3-18") (pinfunction "P$66_P3-18") (pintype "bidirectional"))
      (node (ref "U$2") (pin "P3-19") (pinfunction "P$67_P3-19") (pintype "bidirectional"))
      (node (ref "U$2") (pin "P3-20") (pinfunction "P$68_P3-20") (pintype "bidirectional"))
      (node (ref "U$2") (pin "P4-13") (pinfunction "P$85_P4-13") (pintype "bidirectional"))
      (node (ref "U$2") (pin "P4-14") (pinfunction "P$86_P4-14") (pintype "bidirectional"))
      (node (ref "U$2") (pin "P4-15") (pinfunction "P$87_P4-15") (pintype "bidirectional"))
      (node (ref "U$2") (pin "P4-16") (pinfunction "P$88_P4-16") (pintype "bidirectional"))
    )
    (net (code "22") (name "/R4") (class "Default")
      (node (ref "ESC5_CON4") (pin "A") (pinfunction "A_A") (pintype "bidirectional"))
      (node (ref "U$2") (pin "P3-1") (pinfunction "P$49_P3-1") (pintype "bidirectional"))
      (node (ref "U$2") (pin "P3-2") (pinfunction "P$50_P3-2") (pintype "bidirectional"))
      (node (ref "U$2") (pin "P3-3") (pinfunction "P$51_P3-3") (pintype "bidirectional"))
      (node (ref "U$2") (pin "P3-4") (pinfunction "P$52_P3-4") (pintype "bidirectional"))
      (node (ref "U$2") (pin "P3-5") (pinfunction "P$53_P3-5") (pintype "bidirectional"))
      (node (ref "U$2") (pin "P3-6") (pinfunction "P$54_P3-6") (pintype "bidirectional"))
      (node (ref "U$2") (pin "P3-7") (pinfunction "P$55_P3-7") (pintype "bidirectional"))
      (node (ref "U$2") (pin "P3-8") (pinfunction "P$56_P3-8") (pintype "bidirectional"))
    )
    (net (code "23") (name "/R5") (class "Default")
      (node (ref "ESC5_CON5") (pin "A") (pinfunction "A_A") (pintype "bidirectional"))
      (node (ref "U$3") (pin "P1-1") (pinfunction "P$1_P1-1") (pintype "bidirectional"))
      (node (ref "U$3") (pin "P1-2") (pinfunction "P$2_P1-2") (pintype "bidirectional"))
      (node (ref "U$3") (pin "P1-21") (pinfunction "P$21_P1-21") (pintype "bidirectional"))
      (node (ref "U$3") (pin "P1-22") (pinfunction "P$22_P1-22") (pintype "bidirectional"))
      (node (ref "U$3") (pin "P1-23") (pinfunction "P$23_P1-23") (pintype "bidirectional"))
      (node (ref "U$3") (pin "P1-24") (pinfunction "P$24_P1-24") (pintype "bidirectional"))
      (node (ref "U$3") (pin "P1-3") (pinfunction "P$3_P1-3") (pintype "bidirectional"))
      (node (ref "U$3") (pin "P1-4") (pinfunction "P$4_P1-4") (pintype "bidirectional"))
    )
    (net (code "24") (name "/R6") (class "Default")
      (node (ref "ESC5_CON6") (pin "A") (pinfunction "A_A") (pintype "bidirectional"))
      (node (ref "U$3") (pin "P1-10") (pinfunction "P$10_P1-10") (pintype "bidirectional"))
      (node (ref "U$3") (pin "P1-11") (pinfunction "P$11_P1-11") (pintype "bidirectional"))
      (node (ref "U$3") (pin "P1-12") (pinfunction "P$12_P1-12") (pintype "bidirectional"))
      (node (ref "U$3") (pin "P1-9") (pinfunction "P$9_P1-9") (pintype "bidirectional"))
      (node (ref "U$3") (pin "P2-13") (pinfunction "P$37_P2-13") (pintype "bidirectional"))
      (node (ref "U$3") (pin "P2-14") (pinfunction "P$38_P2-14") (pintype "bidirectional"))
      (node (ref "U$3") (pin "P2-15") (pinfunction "P$39_P2-15") (pintype "bidirectional"))
      (node (ref "U$3") (pin "P2-16") (pinfunction "P$40_P2-16") (pintype "bidirectional"))
    )
    (net (code "25") (name "/R7") (class "Default")
      (node (ref "ESC5_CON7") (pin "A") (pinfunction "A_A") (pintype "bidirectional"))
      (node (ref "U$3") (pin "P3-17") (pinfunction "P$65_P3-17") (pintype "bidirectional"))
      (node (ref "U$3") (pin "P3-18") (pinfunction "P$66_P3-18") (pintype "bidirectional"))
      (node (ref "U$3") (pin "P3-19") (pinfunction "P$67_P3-19") (pintype "bidirectional"))
      (node (ref "U$3") (pin "P3-20") (pinfunction "P$68_P3-20") (pintype "bidirectional"))
      (node (ref "U$3") (pin "P4-13") (pinfunction "P$85_P4-13") (pintype "bidirectional"))
      (node (ref "U$3") (pin "P4-14") (pinfunction "P$86_P4-14") (pintype "bidirectional"))
      (node (ref "U$3") (pin "P4-15") (pinfunction "P$87_P4-15") (pintype "bidirectional"))
      (node (ref "U$3") (pin "P4-16") (pinfunction "P$88_P4-16") (pintype "bidirectional"))
    )
    (net (code "26") (name "/R8") (class "Default")
      (node (ref "ESC5_CON8") (pin "A") (pinfunction "A_A") (pintype "bidirectional"))
      (node (ref "U$3") (pin "P3-1") (pinfunction "P$49_P3-1") (pintype "bidirectional"))
      (node (ref "U$3") (pin "P3-2") (pinfunction "P$50_P3-2") (pintype "bidirectional"))
      (node (ref "U$3") (pin "P3-3") (pinfunction "P$51_P3-3") (pintype "bidirectional"))
      (node (ref "U$3") (pin "P3-4") (pinfunction "P$52_P3-4") (pintype "bidirectional"))
      (node (ref "U$3") (pin "P3-5") (pinfunction "P$53_P3-5") (pintype "bidirectional"))
      (node (ref "U$3") (pin "P3-6") (pinfunction "P$54_P3-6") (pintype "bidirectional"))
      (node (ref "U$3") (pin "P3-7") (pinfunction "P$55_P3-7") (pintype "bidirectional"))
      (node (ref "U$3") (pin "P3-8") (pinfunction "P$56_P3-8") (pintype "bidirectional"))
    )
    (net (code "27") (name "/R9") (class "Default")
      (node (ref "ESC5_CON9") (pin "A") (pinfunction "A_A") (pintype "bidirectional"))
      (node (ref "U$4") (pin "P1-1") (pinfunction "P$1_P1-1") (pintype "bidirectional"))
      (node (ref "U$4") (pin "P1-2") (pinfunction "P$2_P1-2") (pintype "bidirectional"))
      (node (ref "U$4") (pin "P1-21") (pinfunction "P$21_P1-21") (pintype "bidirectional"))
      (node (ref "U$4") (pin "P1-22") (pinfunction "P$22_P1-22") (pintype "bidirectional"))
      (node (ref "U$4") (pin "P1-23") (pinfunction "P$23_P1-23") (pintype "bidirectional"))
      (node (ref "U$4") (pin "P1-24") (pinfunction "P$24_P1-24") (pintype "bidirectional"))
      (node (ref "U$4") (pin "P1-3") (pinfunction "P$3_P1-3") (pintype "bidirectional"))
      (node (ref "U$4") (pin "P1-4") (pinfunction "P$4_P1-4") (pintype "bidirectional"))
    )
    (net (code "28") (name "/R10") (class "Default")
      (node (ref "ESC5_CON10") (pin "A") (pinfunction "A_A") (pintype "bidirectional"))
      (node (ref "U$4") (pin "P1-10") (pinfunction "P$10_P1-10") (pintype "bidirectional"))
      (node (ref "U$4") (pin "P1-11") (pinfunction "P$11_P1-11") (pintype "bidirectional"))
      (node (ref "U$4") (pin "P1-12") (pinfunction "P$12_P1-12") (pintype "bidirectional"))
      (node (ref "U$4") (pin "P1-9") (pinfunction "P$9_P1-9") (pintype "bidirectional"))
      (node (ref "U$4") (pin "P2-13") (pinfunction "P$37_P2-13") (pintype "bidirectional"))
      (node (ref "U$4") (pin "P2-14") (pinfunction "P$38_P2-14") (pintype "bidirectional"))
      (node (ref "U$4") (pin "P2-15") (pinfunction "P$39_P2-15") (pintype "bidirectional"))
      (node (ref "U$4") (pin "P2-16") (pinfunction "P$40_P2-16") (pintype "bidirectional"))
    )
    (net (code "29") (name "/R11") (class "Default")
      (node (ref "ESC5_CON11") (pin "A") (pinfunction "A_A") (pintype "bidirectional"))
      (node (ref "U$4") (pin "P3-17") (pinfunction "P$65_P3-17") (pintype "bidirectional"))
      (node (ref "U$4") (pin "P3-18") (pinfunction "P$66_P3-18") (pintype "bidirectional"))
      (node (ref "U$4") (pin "P3-19") (pinfunction "P$67_P3-19") (pintype "bidirectional"))
      (node (ref "U$4") (pin "P3-20") (pinfunction "P$68_P3-20") (pintype "bidirectional"))
      (node (ref "U$4") (pin "P4-13") (pinfunction "P$85_P4-13") (pintype "bidirectional"))
      (node (ref "U$4") (pin "P4-14") (pinfunction "P$86_P4-14") (pintype "bidirectional"))
      (node (ref "U$4") (pin "P4-15") (pinfunction "P$87_P4-15") (pintype "bidirectional"))
      (node (ref "U$4") (pin "P4-16") (pinfunction "P$88_P4-16") (pintype "bidirectional"))
    )
    (net (code "30") (name "/R12") (class "Default")
      (node (ref "ESC5_CON12") (pin "A") (pinfunction "A_A") (pintype "bidirectional"))
      (node (ref "U$4") (pin "P3-1") (pinfunction "P$49_P3-1") (pintype "bidirectional"))
      (node (ref "U$4") (pin "P3-2") (pinfunction "P$50_P3-2") (pintype "bidirectional"))
      (node (ref "U$4") (pin "P3-3") (pinfunction "P$51_P3-3") (pintype "bidirectional"))
      (node (ref "U$4") (pin "P3-4") (pinfunction "P$52_P3-4") (pintype "bidirectional"))
      (node (ref "U$4") (pin "P3-5") (pinfunction "P$53_P3-5") (pintype "bidirectional"))
      (node (ref "U$4") (pin "P3-6") (pinfunction "P$54_P3-6") (pintype "bidirectional"))
      (node (ref "U$4") (pin "P3-7") (pinfunction "P$55_P3-7") (pintype "bidirectional"))
      (node (ref "U$4") (pin "P3-8") (pinfunction "P$56_P3-8") (pintype "bidirectional"))
    )
    (net (code "31") (name "/Y1") (class "Default")
      (node (ref "ESC5_CON1") (pin "B") (pinfunction "B_B") (pintype "bidirectional"))
      (node (ref "U$2") (pin "P1-17") (pinfunction "P$17_P1-17") (pintype "bidirectional"))
      (node (ref "U$2") (pin "P1-18") (pinfunction "P$18_P1-18") (pintype "bidirectional"))
      (node (ref "U$2") (pin "P1-19") (pinfunction "P$19_P1-19") (pintype "bidirectional"))
      (node (ref "U$2") (pin "P1-20") (pinfunction "P$20_P1-20") (pintype "bidirectional"))
      (node (ref "U$2") (pin "P2-21") (pinfunction "P$45_P2-21") (pintype "bidirectional"))
      (node (ref "U$2") (pin "P2-22") (pinfunction "P$46_P2-22") (pintype "bidirectional"))
      (node (ref "U$2") (pin "P2-23") (pinfunction "P$47_P2-23") (pintype "bidirectional"))
      (node (ref "U$2") (pin "P2-24") (pinfunction "P$48_P2-24") (pintype "bidirectional"))
    )
    (net (code "32") (name "/Y2") (class "Default")
      (node (ref "ESC5_CON2") (pin "B") (pinfunction "B_B") (pintype "bidirectional"))
      (node (ref "U$2") (pin "P1-5") (pinfunction "P$5_P1-5") (pintype "bidirectional"))
      (node (ref "U$2") (pin "P1-6") (pinfunction "P$6_P1-6") (pintype "bidirectional"))
      (node (ref "U$2") (pin "P1-7") (pinfunction "P$7_P1-7") (pintype "bidirectional"))
      (node (ref "U$2") (pin "P1-8") (pinfunction "P$8_P1-8") (pintype "bidirectional"))
      (node (ref "U$2") (pin "P2-10") (pinfunction "P$34_P2-10") (pintype "bidirectional"))
      (node (ref "U$2") (pin "P2-11") (pinfunction "P$35_P2-11") (pintype "bidirectional"))
      (node (ref "U$2") (pin "P2-12") (pinfunction "P$36_P2-12") (pintype "bidirectional"))
      (node (ref "U$2") (pin "P2-9") (pinfunction "P$33_P2-9") (pintype "bidirectional"))
    )
    (net (code "33") (name "/Y3") (class "Default")
      (node (ref "ESC5_CON3") (pin "B") (pinfunction "B_B") (pintype "bidirectional"))
      (node (ref "U$2") (pin "P4-17") (pinfunction "P$89_P4-17") (pintype "bidirectional"))
      (node (ref "U$2") (pin "P4-18") (pinfunction "P$90_P4-18") (pintype "bidirectional"))
      (node (ref "U$2") (pin "P4-19") (pinfunction "P$91_P4-19") (pintype "bidirectional"))
      (node (ref "U$2") (pin "P4-20") (pinfunction "P$92_P4-20") (pintype "bidirectional"))
      (node (ref "U$2") (pin "P4-25") (pinfunction "P$93_P4-25") (pintype "bidirectional"))
      (node (ref "U$2") (pin "P4-26") (pinfunction "P$94_P4-26") (pintype "bidirectional"))
      (node (ref "U$2") (pin "P4-27") (pinfunction "P$95_P4-27") (pintype "bidirectional"))
      (node (ref "U$2") (pin "P4-28") (pinfunction "P$96_P4-28") (pintype "bidirectional"))
    )
    (net (code "34") (name "/Y4") (class "Default")
      (node (ref "ESC5_CON4") (pin "B") (pinfunction "B_B") (pintype "bidirectional"))
      (node (ref "U$2") (pin "P3-10") (pinfunction "P$58_P3-10") (pintype "bidirectional"))
      (node (ref "U$2") (pin "P3-11") (pinfunction "P$59_P3-11") (pintype "bidirectional"))
      (node (ref "U$2") (pin "P3-12") (pinfunction "P$60_P3-12") (pintype "bidirectional"))
      (node (ref "U$2") (pin "P3-9") (pinfunction "P$57_P3-9") (pintype "bidirectional"))
      (node (ref "U$2") (pin "P4-1") (pinfunction "P$73_P4-1") (pintype "bidirectional"))
      (node (ref "U$2") (pin "P4-2") (pinfunction "P$74_P4-2") (pintype "bidirectional"))
      (node (ref "U$2") (pin "P4-3") (pinfunction "P$75_P4-3") (pintype "bidirectional"))
      (node (ref "U$2") (pin "P4-4") (pinfunction "P$76_P4-4") (pintype "bidirectional"))
    )
    (net (code "35") (name "/Y5") (class "Default")
      (node (ref "ESC5_CON5") (pin "B") (pinfunction "B_B") (pintype "bidirectional"))
      (node (ref "U$3") (pin "P1-17") (pinfunction "P$17_P1-17") (pintype "bidirectional"))
      (node (ref "U$3") (pin "P1-18") (pinfunction "P$18_P1-18") (pintype "bidirectional"))
      (node (ref "U$3") (pin "P1-19") (pinfunction "P$19_P1-19") (pintype "bidirectional"))
      (node (ref "U$3") (pin "P1-20") (pinfunction "P$20_P1-20") (pintype "bidirectional"))
      (node (ref "U$3") (pin "P2-21") (pinfunction "P$45_P2-21") (pintype "bidirectional"))
      (node (ref "U$3") (pin "P2-22") (pinfunction "P$46_P2-22") (pintype "bidirectional"))
      (node (ref "U$3") (pin "P2-23") (pinfunction "P$47_P2-23") (pintype "bidirectional"))
      (node (ref "U$3") (pin "P2-24") (pinfunction "P$48_P2-24") (pintype "bidirectional"))
    )
    (net (code "36") (name "/Y6") (class "Default")
      (node (ref "ESC5_CON6") (pin "B") (pinfunction "B_B") (pintype "bidirectional"))
      (node (ref "U$3") (pin "P1-5") (pinfunction "P$5_P1-5") (pintype "bidirectional"))
      (node (ref "U$3") (pin "P1-6") (pinfunction "P$6_P1-6") (pintype "bidirectional"))
      (node (ref "U$3") (pin "P1-7") (pinfunction "P$7_P1-7") (pintype "bidirectional"))
      (node (ref "U$3") (pin "P1-8") (pinfunction "P$8_P1-8") (pintype "bidirectional"))
      (node (ref "U$3") (pin "P2-10") (pinfunction "P$34_P2-10") (pintype "bidirectional"))
      (node (ref "U$3") (pin "P2-11") (pinfunction "P$35_P2-11") (pintype "bidirectional"))
      (node (ref "U$3") (pin "P2-12") (pinfunction "P$36_P2-12") (pintype "bidirectional"))
      (node (ref "U$3") (pin "P2-9") (pinfunction "P$33_P2-9") (pintype "bidirectional"))
    )
    (net (code "37") (name "/Y7") (class "Default")
      (node (ref "ESC5_CON7") (pin "B") (pinfunction "B_B") (pintype "bidirectional"))
      (node (ref "U$3") (pin "P4-17") (pinfunction "P$89_P4-17") (pintype "bidirectional"))
      (node (ref "U$3") (pin "P4-18") (pinfunction "P$90_P4-18") (pintype "bidirectional"))
      (node (ref "U$3") (pin "P4-19") (pinfunction "P$91_P4-19") (pintype "bidirectional"))
      (node (ref "U$3") (pin "P4-20") (pinfunction "P$92_P4-20") (pintype "bidirectional"))
      (node (ref "U$3") (pin "P4-25") (pinfunction "P$93_P4-25") (pintype "bidirectional"))
      (node (ref "U$3") (pin "P4-26") (pinfunction "P$94_P4-26") (pintype "bidirectional"))
      (node (ref "U$3") (pin "P4-27") (pinfunction "P$95_P4-27") (pintype "bidirectional"))
      (node (ref "U$3") (pin "P4-28") (pinfunction "P$96_P4-28") (pintype "bidirectional"))
    )
    (net (code "38") (name "/Y8") (class "Default")
      (node (ref "ESC5_CON8") (pin "B") (pinfunction "B_B") (pintype "bidirectional"))
      (node (ref "U$3") (pin "P3-10") (pinfunction "P$58_P3-10") (pintype "bidirectional"))
      (node (ref "U$3") (pin "P3-11") (pinfunction "P$59_P3-11") (pintype "bidirectional"))
      (node (ref "U$3") (pin "P3-12") (pinfunction "P$60_P3-12") (pintype "bidirectional"))
      (node (ref "U$3") (pin "P3-9") (pinfunction "P$57_P3-9") (pintype "bidirectional"))
      (node (ref "U$3") (pin "P4-1") (pinfunction "P$73_P4-1") (pintype "bidirectional"))
      (node (ref "U$3") (pin "P4-2") (pinfunction "P$74_P4-2") (pintype "bidirectional"))
      (node (ref "U$3") (pin "P4-3") (pinfunction "P$75_P4-3") (pintype "bidirectional"))
      (node (ref "U$3") (pin "P4-4") (pinfunction "P$76_P4-4") (pintype "bidirectional"))
    )
    (net (code "39") (name "/Y9") (class "Default")
      (node (ref "ESC5_CON9") (pin "B") (pinfunction "B_B") (pintype "bidirectional"))
      (node (ref "U$4") (pin "P1-17") (pinfunction "P$17_P1-17") (pintype "bidirectional"))
      (node (ref "U$4") (pin "P1-18") (pinfunction "P$18_P1-18") (pintype "bidirectional"))
      (node (ref "U$4") (pin "P1-19") (pinfunction "P$19_P1-19") (pintype "bidirectional"))
      (node (ref "U$4") (pin "P1-20") (pinfunction "P$20_P1-20") (pintype "bidirectional"))
      (node (ref "U$4") (pin "P2-21") (pinfunction "P$45_P2-21") (pintype "bidirectional"))
      (node (ref "U$4") (pin "P2-22") (pinfunction "P$46_P2-22") (pintype "bidirectional"))
      (node (ref "U$4") (pin "P2-23") (pinfunction "P$47_P2-23") (pintype "bidirectional"))
      (node (ref "U$4") (pin "P2-24") (pinfunction "P$48_P2-24") (pintype "bidirectional"))
    )
    (net (code "40") (name "/Y10") (class "Default")
      (node (ref "ESC5_CON10") (pin "B") (pinfunction "B_B") (pintype "bidirectional"))
      (node (ref "U$4") (pin "P1-5") (pinfunction "P$5_P1-5") (pintype "bidirectional"))
      (node (ref "U$4") (pin "P1-6") (pinfunction "P$6_P1-6") (pintype "bidirectional"))
      (node (ref "U$4") (pin "P1-7") (pinfunction "P$7_P1-7") (pintype "bidirectional"))
      (node (ref "U$4") (pin "P1-8") (pinfunction "P$8_P1-8") (pintype "bidirectional"))
      (node (ref "U$4") (pin "P2-10") (pinfunction "P$34_P2-10") (pintype "bidirectional"))
      (node (ref "U$4") (pin "P2-11") (pinfunction "P$35_P2-11") (pintype "bidirectional"))
      (node (ref "U$4") (pin "P2-12") (pinfunction "P$36_P2-12") (pintype "bidirectional"))
      (node (ref "U$4") (pin "P2-9") (pinfunction "P$33_P2-9") (pintype "bidirectional"))
    )
    (net (code "41") (name "/Y11") (class "Default")
      (node (ref "ESC5_CON11") (pin "B") (pinfunction "B_B") (pintype "bidirectional"))
      (node (ref "U$4") (pin "P4-17") (pinfunction "P$89_P4-17") (pintype "bidirectional"))
      (node (ref "U$4") (pin "P4-18") (pinfunction "P$90_P4-18") (pintype "bidirectional"))
      (node (ref "U$4") (pin "P4-19") (pinfunction "P$91_P4-19") (pintype "bidirectional"))
      (node (ref "U$4") (pin "P4-20") (pinfunction "P$92_P4-20") (pintype "bidirectional"))
      (node (ref "U$4") (pin "P4-25") (pinfunction "P$93_P4-25") (pintype "bidirectional"))
      (node (ref "U$4") (pin "P4-26") (pinfunction "P$94_P4-26") (pintype "bidirectional"))
      (node (ref "U$4") (pin "P4-27") (pinfunction "P$95_P4-27") (pintype "bidirectional"))
      (node (ref "U$4") (pin "P4-28") (pinfunction "P$96_P4-28") (pintype "bidirectional"))
    )
    (net (code "42") (name "/Y12") (class "Default")
      (node (ref "ESC5_CON12") (pin "B") (pinfunction "B_B") (pintype "bidirectional"))
      (node (ref "U$4") (pin "P3-10") (pinfunction "P$58_P3-10") (pintype "bidirectional"))
      (node (ref "U$4") (pin "P3-11") (pinfunction "P$59_P3-11") (pintype "bidirectional"))
      (node (ref "U$4") (pin "P3-12") (pinfunction "P$60_P3-12") (pintype "bidirectional"))
      (node (ref "U$4") (pin "P3-9") (pinfunction "P$57_P3-9") (pintype "bidirectional"))
      (node (ref "U$4") (pin "P4-1") (pinfunction "P$73_P4-1") (pintype "bidirectional"))
      (node (ref "U$4") (pin "P4-2") (pinfunction "P$74_P4-2") (pintype "bidirectional"))
      (node (ref "U$4") (pin "P4-3") (pinfunction "P$75_P4-3") (pintype "bidirectional"))
      (node (ref "U$4") (pin "P4-4") (pinfunction "P$76_P4-4") (pintype "bidirectional"))
    )
    (net (code "43") (name "unconnected-(U$2-Pad17)") (class "Default")
      (node (ref "U$2") (pin "17") (pinfunction "17_17") (pintype "bidirectional"))
    )
    (net (code "44") (name "unconnected-(U$2-Pad18)") (class "Default")
      (node (ref "U$2") (pin "18") (pinfunction "18_18") (pintype "bidirectional"))
    )
    (net (code "45") (name "unconnected-(U$2-Pad19)") (class "Default")
      (node (ref "U$2") (pin "19") (pinfunction "19_19") (pintype "bidirectional"))
    )
    (net (code "46") (name "unconnected-(U$2-Pad20)") (class "Default")
      (node (ref "U$2") (pin "20") (pinfunction "20_20") (pintype "bidirectional"))
    )
    (net (code "47") (name "unconnected-(U$2-Pad21)") (class "Default")
      (node (ref "U$2") (pin "21") (pinfunction "21_21") (pintype "bidirectional"))
    )
    (net (code "48") (name "unconnected-(U$2-Pad22)") (class "Default")
      (node (ref "U$2") (pin "22") (pinfunction "22_22") (pintype "bidirectional"))
    )
    (net (code "49") (name "unconnected-(U$3-Pad17)") (class "Default")
      (node (ref "U$3") (pin "17") (pinfunction "17_17") (pintype "bidirectional"))
    )
    (net (code "50") (name "unconnected-(U$3-Pad18)") (class "Default")
      (node (ref "U$3") (pin "18") (pinfunction "18_18") (pintype "bidirectional"))
    )
    (net (code "51") (name "unconnected-(U$3-Pad19)") (class "Default")
      (node (ref "U$3") (pin "19") (pinfunction "19_19") (pintype "bidirectional"))
    )
    (net (code "52") (name "unconnected-(U$3-Pad20)") (class "Default")
      (node (ref "U$3") (pin "20") (pinfunction "20_20") (pintype "bidirectional"))
    )
    (net (code "53") (name "unconnected-(U$3-Pad21)") (class "Default")
      (node (ref "U$3") (pin "21") (pinfunction "21_21") (pintype "bidirectional"))
    )
    (net (code "54") (name "unconnected-(U$3-Pad22)") (class "Default")
      (node (ref "U$3") (pin "22") (pinfunction "22_22") (pintype "bidirectional"))
    )
    (net (code "55") (name "unconnected-(U$4-Pad17)") (class "Default")
      (node (ref "U$4") (pin "17") (pinfunction "17_17") (pintype "bidirectional"))
    )
    (net (code "56") (name "unconnected-(U$4-Pad18)") (class "Default")
      (node (ref "U$4") (pin "18") (pinfunction "18_18") (pintype "bidirectional"))
    )
    (net (code "57") (name "unconnected-(U$4-Pad19)") (class "Default")
      (node (ref "U$4") (pin "19") (pinfunction "19_19") (pintype "bidirectional"))
    )
    (net (code "58") (name "unconnected-(U$4-Pad20)") (class "Default")
      (node (ref "U$4") (pin "20") (pinfunction "20_20") (pintype "bidirectional"))
    )
    (net (code "59") (name "unconnected-(U$4-Pad21)") (class "Default")
      (node (ref "U$4") (pin "21") (pinfunction "21_21") (pintype "bidirectional"))
    )
    (net (code "60") (name "unconnected-(U$4-Pad22)") (class "Default")
      (node (ref "U$4") (pin "22") (pinfunction "22_22") (pintype "bidirectional"))
    )
    (net (code "61") (name "unconnected-(U$5-Pad1)") (class "Default")
      (node (ref "U$5") (pin "1") (pinfunction "1_1") (pintype "bidirectional"))
    )
    (net (code "62") (name "unconnected-(U$6-Pad1)") (class "Default")
      (node (ref "U$6") (pin "1") (pinfunction "1_1") (pintype "bidirectional"))
    )
    (net (code "63") (name "unconnected-(U$7-Pad1)") (class "Default")
      (node (ref "U$7") (pin "1") (pinfunction "1_1") (pintype "bidirectional"))
    )
    (net (code "64") (name "unconnected-(U$8-Pad1)") (class "Default")
      (node (ref "U$8") (pin "1") (pinfunction "1_1") (pintype "bidirectional"))
    )
    (net (code "65") (name "unconnected-(U$9-Pad1)") (class "Default")
      (node (ref "U$9") (pin "1") (pinfunction "1_1") (pintype "bidirectional"))
    )
    (net (code "66") (name "unconnected-(U$10-Pad1)") (class "Default")
      (node (ref "U$10") (pin "1") (pinfunction "1_1") (pintype "bidirectional"))
    )
    (net (code "67") (name "unconnected-(U$10-Pad4)") (class "Default")
      (node (ref "U$10") (pin "4") (pinfunction "4_4") (pintype "bidirectional"))
    )
    (net (code "68") (name "unconnected-(U$11-Pad1)") (class "Default")
      (node (ref "U$11") (pin "1") (pinfunction "1_1") (pintype "bidirectional"))
    )
    (net (code "69") (name "unconnected-(U$12-Pad1)") (class "Default")
      (node (ref "U$12") (pin "1") (pinfunction "1_1") (pintype "bidirectional"))
    )
    (net (code "70") (name "unconnected-(U$12-Pad4)") (class "Default")
      (node (ref "U$12") (pin "4") (pinfunction "4_4") (pintype "bidirectional"))
    )
    (net (code "71") (name "unconnected-(U$15-Pad1)") (class "Default")
      (node (ref "U$15") (pin "1") (pinfunction "1_1") (pintype "bidirectional"))
    )
    (net (code "72") (name "unconnected-(U$16-Pad1)") (class "Default")
      (node (ref "U$16") (pin "1") (pinfunction "1_1") (pintype "bidirectional"))
    )
  )
)
